# VCA.net
KiCad netlist of a schematic drawn in Altium Designer
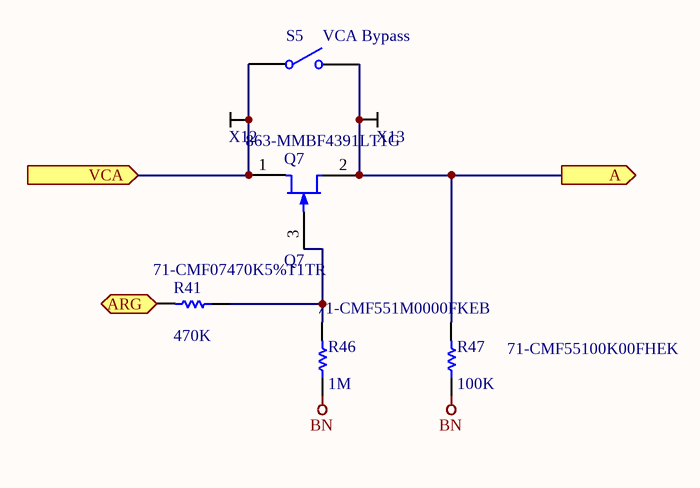
[diagram p0: VCA.SchDoc]

(export (version "E")
  (design (tool "Eeschema 10.0.6"))
  (components
    (comp (ref "Q7")
      (value "Q7")
      (footprint "ONSC-SOT-23-3-318-08_V")
      (description "JFET Switching Transistor, N-Channel, 3-Pin SOT-23, Tape and Reel")
      (fields
        (field (name "MANUFACTURER") "On Semiconductor")
        (field (name "PARTNUMBER") "MMBF4391LT1")
        (field (name "SUPPLIER PART NUMBER 2") "863-MMBF4391LT1G")
      )
      (libsource (lib "ON Semi JFETs") (part "MMBF4391LT1"))
    )
    (comp (ref "R41")
      (value "470K")
      (footprint "AXIAL-0.3")
      (description "Resistor")
      (fields
        (field (name "SUPPLIER PART NUMBER 1") "71-CMF07470K5%T1TR")
        (field (name "MANUFACTURER") "Vishay / Dale")
        (field (name "MANUFACTURER PART NUMBER") "CMF07470K00JKR6")
        (field (name "PUBLISHER") "Altium Limited")
      )
      (libsource (lib "Miscellaneous Devices") (part "Res1"))
    )
    (comp (ref "R46")
      (value "1M")
      (footprint "AXIAL-0.3")
      (description "Resistor")
      (fields
        (field (name "SUPPLIER PART NUMBER 1") "71-CMF551M0000FKEB")
        (field (name "MANUFACTURER") "Vishay / Dale")
        (field (name "MANUFACTURER PART NUMBER") "CMF551M0000FKEB")
        (field (name "PUBLISHER") "Altium Limited")
      )
      (libsource (lib "Miscellaneous Devices") (part "Res1"))
    )
    (comp (ref "R47")
      (value "100K")
      (footprint "AXIAL-0.3")
      (description "Resistor")
      (fields
        (field (name "SUPPLIER PART NUMBER 1") "71-CMF55100K00FHEK")
        (field (name "MANUFACTURER") "Vishay / Dale")
        (field (name "MANUFACTURER PART NUMBER") "CMF55100K00FHEK")
        (field (name "PUBLISHER") "Altium Limited")
      )
      (libsource (lib "Miscellaneous Devices") (part "Res1"))
    )
    (comp (ref "S5")
      (value "VCA Bypass")
      (footprint "SPST-2")
      (description "Single-Pole, Single-Throw Switch")
      (fields (field (name "PUBLISHER") "Altium Limited"))
      (libsource (lib "Miscellaneous Devices") (part "SW-SPST"))
    )
    (comp (ref "X12") (value "X12") (footprint "Pad") (libsource (lib "MyLibrary") (part "Pad")))
    (comp (ref "X13") (value "X13") (footprint "Pad") (libsource (lib "MyLibrary") (part "Pad")))
  )
  (nets
    (net (code "1") (name "/A") (class "Default")
      (node (ref "Q7") (pin "2") (pinfunction "S_2") (pintype "passive"))
      (node (ref "R47") (pin "2") (pinfunction "2_2") (pintype "passive"))
      (node (ref "S5") (pin "2") (pinfunction "NO_2") (pintype "passive"))
      (node (ref "X13") (pin "1") (pinfunction "1_1") (pintype "passive"))
    )
    (net (code "2") (name "/ARG") (class "Default")
      (node (ref "R41") (pin "2") (pinfunction "2_2") (pintype "passive"))
    )
    (net (code "3") (name "/VCA") (class "Default")
      (node (ref "Q7") (pin "1") (pinfunction "D_1") (pintype "passive"))
      (node (ref "S5") (pin "1") (pinfunction "COMMON_1") (pintype "passive"))
      (node (ref "X12") (pin "1") (pinfunction "1_1") (pintype "passive"))
    )
    (net (code "4") (name "BN") (class "Default")
      (node (ref "R46") (pin "1") (pinfunction "1_1") (pintype "passive"))
      (node (ref "R47") (pin "1") (pinfunction "1_1") (pintype "passive"))
    )
    (net (code "5") (name "Net-(Q7-G)") (class "Default")
      (node (ref "Q7") (pin "3") (pinfunction "G_3") (pintype "passive"))
      (node (ref "R41") (pin "1") (pinfunction "1_1") (pintype "passive"))
      (node (ref "R46") (pin "2") (pinfunction "2_2") (pintype "passive"))
    )
  )
)
